# DisplayCard.net
KiCad netlist of a schematic drawn in EAGLE
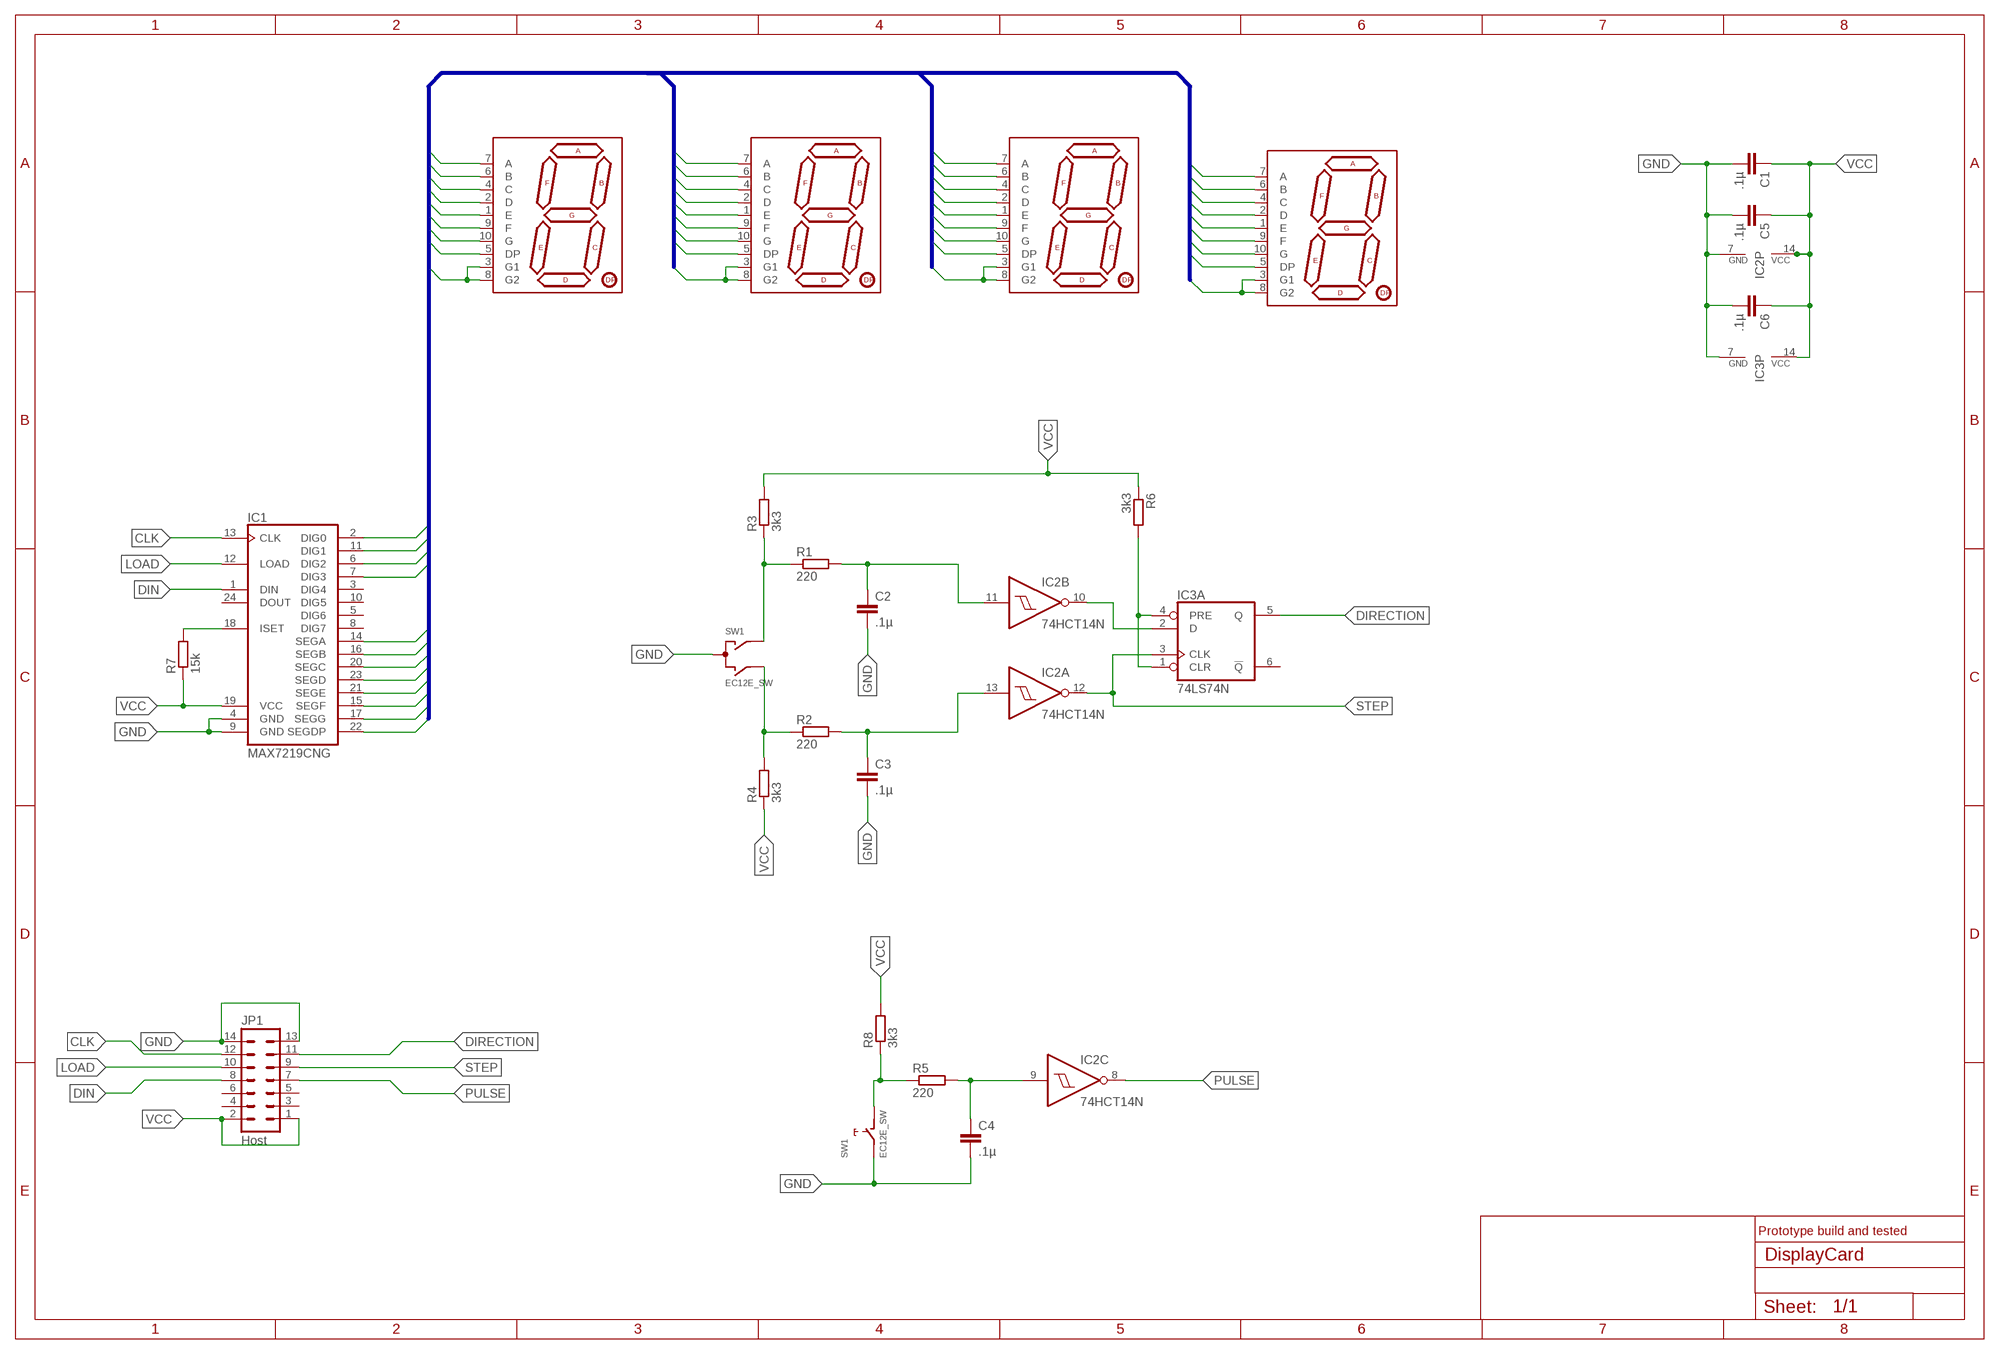
[diagram p0: schematic, sheet 1]

(export (version "E")
  (design (tool "Eeschema 10.0.6"))
  (components
    (comp (ref "C1")
      (value ".1µ")
      (footprint "eagle-import:C025-024X044")
      (libsource (lib "eagle-import") (part "resistor_C-EU025-024X044"))
    )
    (comp (ref "C2")
      (value ".1µ")
      (footprint "eagle-import:C025-024X044")
      (libsource (lib "eagle-import") (part "C-EU025-024X044"))
    )
    (comp (ref "C3")
      (value ".1µ")
      (footprint "eagle-import:C025-024X044")
      (libsource (lib "eagle-import") (part "C-EU025-024X044"))
    )
    (comp (ref "C4")
      (value ".1µ")
      (footprint "eagle-import:C025-024X044")
      (libsource (lib "eagle-import") (part "C-EU025-024X044"))
    )
    (comp (ref "C5")
      (value ".1µ")
      (footprint "eagle-import:C025-024X044")
      (libsource (lib "eagle-import") (part "resistor_C-EU025-024X044"))
    )
    (comp (ref "C6")
      (value ".1µ")
      (footprint "eagle-import:C025-024X044")
      (libsource (lib "eagle-import") (part "resistor_C-EU025-024X044"))
    )
    (comp (ref "DIGI4")
      (value "7-SEGMENT-DISPLAYPTH")
      (footprint "eagle-import:7-SEGMENT-DISPLAY")
      (libsource (lib "eagle-import") (part "7-SEGMENT-DISPLAYPTH"))
    )
    (comp (ref "DIGIT1")
      (value "7-SEGMENT-DISPLAYPTH")
      (footprint "eagle-import:7-SEGMENT-DISPLAY")
      (libsource (lib "eagle-import") (part "7-SEGMENT-DISPLAYPTH"))
    )
    (comp (ref "DIGIT2")
      (value "7-SEGMENT-DISPLAYPTH")
      (footprint "eagle-import:7-SEGMENT-DISPLAY")
      (libsource (lib "eagle-import") (part "7-SEGMENT-DISPLAYPTH"))
    )
    (comp (ref "DIGIT3")
      (value "7-SEGMENT-DISPLAYPTH")
      (footprint "eagle-import:7-SEGMENT-DISPLAY")
      (libsource (lib "eagle-import") (part "7-SEGMENT-DISPLAYPTH"))
    )
    (comp (ref "IC1")
      (value "MAX7219CNG")
      (footprint "eagle-import:DIL24-3")
      (libsource (lib "eagle-import") (part "MAX7219NGC"))
    )
    (comp (ref "IC2")
      (value "74HCT14N")
      (footprint "eagle-import:DIL14")
      (libsource (lib "eagle-import") (part "7414NHCT"))
    )
    (comp (ref "IC3")
      (value "74LS74N")
      (footprint "eagle-import:DIL14")
      (libsource (lib "eagle-import") (part "7474NLS"))
    )
    (comp (ref "JP1")
      (value "Host")
      (footprint "eagle-import:ML14L")
      (libsource (lib "eagle-import") (part "ML14L"))
    )
    (comp (ref "R1")
      (value "220")
      (footprint "eagle-import:0204_7")
      (libsource (lib "eagle-import") (part "R-EU_0204/7"))
    )
    (comp (ref "R2")
      (value "220")
      (footprint "eagle-import:0204_7")
      (libsource (lib "eagle-import") (part "R-EU_0204/7"))
    )
    (comp (ref "R3")
      (value "3k3")
      (footprint "eagle-import:0204_7")
      (libsource (lib "eagle-import") (part "R-EU_0204/7"))
    )
    (comp (ref "R4")
      (value "3k3")
      (footprint "eagle-import:0204_7")
      (libsource (lib "eagle-import") (part "R-EU_0204/7"))
    )
    (comp (ref "R5")
      (value "220")
      (footprint "eagle-import:0204_7")
      (libsource (lib "eagle-import") (part "R-EU_0204/7"))
    )
    (comp (ref "R6")
      (value "3k3")
      (footprint "eagle-import:0204_7")
      (libsource (lib "eagle-import") (part "R-EU_0204/7"))
    )
    (comp (ref "R7")
      (value "15k")
      (footprint "eagle-import:0204_7")
      (libsource (lib "eagle-import") (part "R-EU_0204/7"))
    )
    (comp (ref "R8")
      (value "3k3")
      (footprint "eagle-import:0204_7")
      (libsource (lib "eagle-import") (part "R-EU_0204/7"))
    )
    (comp (ref "SW1")
      (value "EC12E_SW")
      (footprint "eagle-import:ALPS_EC12E_SW")
      (libsource (lib "eagle-import") (part "EC12E_SW"))
    )
  )
  (nets
    (net (code "1") (name "/A") (class "Default")
      (node (ref "DIGI4") (pin "7") (pinfunction "A_7") (pintype "bidirectional"))
      (node (ref "DIGIT1") (pin "7") (pinfunction "A_7") (pintype "bidirectional"))
      (node (ref "DIGIT2") (pin "7") (pinfunction "A_7") (pintype "bidirectional"))
      (node (ref "DIGIT3") (pin "7") (pinfunction "A_7") (pintype "bidirectional"))
      (node (ref "IC1") (pin "14") (pinfunction "SEGA_14") (pintype "output"))
    )
    (net (code "2") (name "/B") (class "Default")
      (node (ref "DIGI4") (pin "6") (pinfunction "B_6") (pintype "bidirectional"))
      (node (ref "DIGIT1") (pin "6") (pinfunction "B_6") (pintype "bidirectional"))
      (node (ref "DIGIT2") (pin "6") (pinfunction "B_6") (pintype "bidirectional"))
      (node (ref "DIGIT3") (pin "6") (pinfunction "B_6") (pintype "bidirectional"))
      (node (ref "IC1") (pin "16") (pinfunction "SEGB_16") (pintype "output"))
    )
    (net (code "3") (name "/C") (class "Default")
      (node (ref "DIGI4") (pin "4") (pinfunction "C_4") (pintype "bidirectional"))
      (node (ref "DIGIT1") (pin "4") (pinfunction "C_4") (pintype "bidirectional"))
      (node (ref "DIGIT2") (pin "4") (pinfunction "C_4") (pintype "bidirectional"))
      (node (ref "DIGIT3") (pin "4") (pinfunction "C_4") (pintype "bidirectional"))
      (node (ref "IC1") (pin "20") (pinfunction "SEGC_20") (pintype "output"))
    )
    (net (code "4") (name "/D") (class "Default")
      (node (ref "DIGI4") (pin "2") (pinfunction "D_2") (pintype "bidirectional"))
      (node (ref "DIGIT1") (pin "2") (pinfunction "D_2") (pintype "bidirectional"))
      (node (ref "DIGIT2") (pin "2") (pinfunction "D_2") (pintype "bidirectional"))
      (node (ref "DIGIT3") (pin "2") (pinfunction "D_2") (pintype "bidirectional"))
      (node (ref "IC1") (pin "23") (pinfunction "SEGD_23") (pintype "output"))
    )
    (net (code "5") (name "/D0") (class "Default")
      (node (ref "DIGIT1") (pin "3") (pinfunction "G1_3") (pintype "bidirectional"))
      (node (ref "DIGIT1") (pin "8") (pinfunction "G2_8") (pintype "bidirectional"))
      (node (ref "IC1") (pin "2") (pinfunction "DIG0_2") (pintype "output"))
    )
    (net (code "6") (name "/D1") (class "Default")
      (node (ref "DIGIT2") (pin "3") (pinfunction "G1_3") (pintype "bidirectional"))
      (node (ref "DIGIT2") (pin "8") (pinfunction "G2_8") (pintype "bidirectional"))
      (node (ref "IC1") (pin "11") (pinfunction "DIG1_11") (pintype "output"))
    )
    (net (code "7") (name "/D2") (class "Default")
      (node (ref "DIGIT3") (pin "3") (pinfunction "G1_3") (pintype "bidirectional"))
      (node (ref "DIGIT3") (pin "8") (pinfunction "G2_8") (pintype "bidirectional"))
      (node (ref "IC1") (pin "6") (pinfunction "DIG2_6") (pintype "output"))
    )
    (net (code "8") (name "/D3") (class "Default")
      (node (ref "DIGI4") (pin "3") (pinfunction "G1_3") (pintype "bidirectional"))
      (node (ref "DIGI4") (pin "8") (pinfunction "G2_8") (pintype "bidirectional"))
      (node (ref "IC1") (pin "7") (pinfunction "DIG3_7") (pintype "output"))
    )
    (net (code "9") (name "/DP") (class "Default")
      (node (ref "DIGI4") (pin "5") (pinfunction "DP_5") (pintype "bidirectional"))
      (node (ref "DIGIT1") (pin "5") (pinfunction "DP_5") (pintype "bidirectional"))
      (node (ref "DIGIT2") (pin "5") (pinfunction "DP_5") (pintype "bidirectional"))
      (node (ref "IC1") (pin "22") (pinfunction "SEGDP_22") (pintype "output"))
    )
    (net (code "10") (name "/E") (class "Default")
      (node (ref "DIGI4") (pin "1") (pinfunction "E_1") (pintype "bidirectional"))
      (node (ref "DIGIT1") (pin "1") (pinfunction "E_1") (pintype "bidirectional"))
      (node (ref "DIGIT2") (pin "1") (pinfunction "E_1") (pintype "bidirectional"))
      (node (ref "DIGIT3") (pin "1") (pinfunction "E_1") (pintype "bidirectional"))
      (node (ref "IC1") (pin "21") (pinfunction "SEGE_21") (pintype "output"))
    )
    (net (code "11") (name "/F") (class "Default")
      (node (ref "DIGI4") (pin "9") (pinfunction "F_9") (pintype "bidirectional"))
      (node (ref "DIGIT1") (pin "9") (pinfunction "F_9") (pintype "bidirectional"))
      (node (ref "DIGIT2") (pin "9") (pinfunction "F_9") (pintype "bidirectional"))
      (node (ref "DIGIT3") (pin "9") (pinfunction "F_9") (pintype "bidirectional"))
      (node (ref "IC1") (pin "15") (pinfunction "SEGF_15") (pintype "output"))
    )
    (net (code "12") (name "/G") (class "Default")
      (node (ref "DIGI4") (pin "10") (pinfunction "G_10") (pintype "bidirectional"))
      (node (ref "DIGIT1") (pin "10") (pinfunction "G_10") (pintype "bidirectional"))
      (node (ref "DIGIT2") (pin "10") (pinfunction "G_10") (pintype "bidirectional"))
      (node (ref "DIGIT3") (pin "10") (pinfunction "G_10") (pintype "bidirectional"))
      (node (ref "DIGIT3") (pin "5") (pinfunction "DP_5") (pintype "bidirectional"))
      (node (ref "IC1") (pin "17") (pinfunction "SEGG_17") (pintype "output"))
    )
    (net (code "13") (name "CLK") (class "Default")
      (node (ref "IC1") (pin "13") (pinfunction "CLK_13") (pintype "input"))
      (node (ref "JP1") (pin "12") (pinfunction "12_12") (pintype "passive"))
    )
    (net (code "14") (name "DIN") (class "Default")
      (node (ref "IC1") (pin "1") (pinfunction "DIN_1") (pintype "input"))
      (node (ref "JP1") (pin "8") (pinfunction "8_8") (pintype "passive"))
    )
    (net (code "15") (name "DIRECTION") (class "Default")
      (node (ref "IC3") (pin "5") (pinfunction "Q_5") (pintype "output"))
      (node (ref "JP1") (pin "11") (pinfunction "11_11") (pintype "passive"))
    )
    (net (code "16") (name "GND") (class "Default")
      (node (ref "C1") (pin "2") (pinfunction "2_2") (pintype "passive"))
      (node (ref "C2") (pin "2") (pinfunction "2_2") (pintype "passive"))
      (node (ref "C3") (pin "2") (pinfunction "2_2") (pintype "passive"))
      (node (ref "C4") (pin "2") (pinfunction "2_2") (pintype "passive"))
      (node (ref "C5") (pin "2") (pinfunction "2_2") (pintype "passive"))
      (node (ref "C6") (pin "2") (pinfunction "2_2") (pintype "passive"))
      (node (ref "IC1") (pin "4") (pinfunction "GND_4") (pintype "power_in"))
      (node (ref "IC1") (pin "9") (pinfunction "GND_9") (pintype "power_in"))
      (node (ref "IC2") (pin "7") (pinfunction "GND_7") (pintype "power_in"))
      (node (ref "IC3") (pin "7") (pinfunction "GND_7") (pintype "power_in"))
      (node (ref "JP1") (pin "13") (pinfunction "13_13") (pintype "passive"))
      (node (ref "JP1") (pin "14") (pinfunction "14_14") (pintype "passive"))
      (node (ref "SW1") (pin "C") (pinfunction "C_C") (pintype "passive"))
      (node (ref "SW1") (pin "E") (pinfunction "2_E") (pintype "passive"))
    )
    (net (code "17") (name "LOAD") (class "Default")
      (node (ref "IC1") (pin "12") (pinfunction "LOAD_12") (pintype "input"))
      (node (ref "JP1") (pin "10") (pinfunction "10_10") (pintype "passive"))
    )
    (net (code "18") (name "Net-(IC1-ISET)") (class "Default")
      (node (ref "IC1") (pin "18") (pinfunction "ISET_18") (pintype "input"))
      (node (ref "R7") (pin "2") (pinfunction "2_2") (pintype "passive"))
    )
    (net (code "19") (name "Net-(IC2A-I)") (class "Default")
      (node (ref "C3") (pin "1") (pinfunction "1_1") (pintype "passive"))
      (node (ref "IC2") (pin "13") (pinfunction "I_13") (pintype "input"))
      (node (ref "R2") (pin "2") (pinfunction "2_2") (pintype "passive"))
    )
    (net (code "20") (name "Net-(IC2B-I)") (class "Default")
      (node (ref "C2") (pin "1") (pinfunction "1_1") (pintype "passive"))
      (node (ref "IC2") (pin "11") (pinfunction "I_11") (pintype "input"))
      (node (ref "R1") (pin "2") (pinfunction "2_2") (pintype "passive"))
    )
    (net (code "21") (name "Net-(IC2B-O)") (class "Default")
      (node (ref "IC2") (pin "10") (pinfunction "O_10") (pintype "output"))
      (node (ref "IC3") (pin "2") (pinfunction "D_2") (pintype "input"))
    )
    (net (code "22") (name "Net-(IC2C-I)") (class "Default")
      (node (ref "C4") (pin "1") (pinfunction "1_1") (pintype "passive"))
      (node (ref "IC2") (pin "9") (pinfunction "I_9") (pintype "input"))
      (node (ref "R5") (pin "2") (pinfunction "2_2") (pintype "passive"))
    )
    (net (code "23") (name "Net-(IC3A-CLR)") (class "Default")
      (node (ref "IC3") (pin "1") (pinfunction "CLR_1") (pintype "input"))
      (node (ref "IC3") (pin "4") (pinfunction "PRE_4") (pintype "input"))
      (node (ref "R6") (pin "2") (pinfunction "2_2") (pintype "passive"))
    )
    (net (code "24") (name "Net-(R1-Pad1)") (class "Default")
      (node (ref "R1") (pin "1") (pinfunction "1_1") (pintype "passive"))
      (node (ref "R3") (pin "1") (pinfunction "1_1") (pintype "passive"))
      (node (ref "SW1") (pin "A") (pinfunction "A_A") (pintype "passive"))
    )
    (net (code "25") (name "Net-(R2-Pad1)") (class "Default")
      (node (ref "R2") (pin "1") (pinfunction "1_1") (pintype "passive"))
      (node (ref "R4") (pin "2") (pinfunction "2_2") (pintype "passive"))
      (node (ref "SW1") (pin "B") (pinfunction "B_B") (pintype "passive"))
    )
    (net (code "26") (name "Net-(SW1B-1)") (class "Default")
      (node (ref "R5") (pin "1") (pinfunction "1_1") (pintype "passive"))
      (node (ref "R8") (pin "1") (pinfunction "1_1") (pintype "passive"))
      (node (ref "SW1") (pin "D") (pinfunction "1_D") (pintype "passive"))
    )
    (net (code "27") (name "PULSE") (class "Default")
      (node (ref "IC2") (pin "8") (pinfunction "O_8") (pintype "output"))
      (node (ref "JP1") (pin "7") (pinfunction "7_7") (pintype "passive"))
    )
    (net (code "28") (name "STEP") (class "Default")
      (node (ref "IC2") (pin "12") (pinfunction "O_12") (pintype "output"))
      (node (ref "IC3") (pin "3") (pinfunction "CLK_3") (pintype "input"))
      (node (ref "JP1") (pin "9") (pinfunction "9_9") (pintype "passive"))
    )
    (net (code "29") (name "VCC") (class "Default")
      (node (ref "C1") (pin "1") (pinfunction "1_1") (pintype "passive"))
      (node (ref "C5") (pin "1") (pinfunction "1_1") (pintype "passive"))
      (node (ref "C6") (pin "1") (pinfunction "1_1") (pintype "passive"))
      (node (ref "IC1") (pin "19") (pinfunction "VCC_19") (pintype "power_in"))
      (node (ref "IC2") (pin "14") (pinfunction "VCC_14") (pintype "power_in"))
      (node (ref "IC3") (pin "14") (pinfunction "VCC_14") (pintype "power_in"))
      (node (ref "JP1") (pin "1") (pinfunction "1_1") (pintype "passive"))
      (node (ref "JP1") (pin "2") (pinfunction "2_2") (pintype "passive"))
      (node (ref "R3") (pin "2") (pinfunction "2_2") (pintype "passive"))
      (node (ref "R4") (pin "1") (pinfunction "1_1") (pintype "passive"))
      (node (ref "R6") (pin "1") (pinfunction "1_1") (pintype "passive"))
      (node (ref "R7") (pin "1") (pinfunction "1_1") (pintype "passive"))
      (node (ref "R8") (pin "2") (pinfunction "2_2") (pintype "passive"))
    )
    (net (code "30") (name "unconnected-(IC1-DIG4-Pad3)") (class "Default")
      (node (ref "IC1") (pin "3") (pinfunction "DIG4_3") (pintype "output"))
    )
    (net (code "31") (name "unconnected-(IC1-DIG5-Pad10)") (class "Default")
      (node (ref "IC1") (pin "10") (pinfunction "DIG5_10") (pintype "output"))
    )
    (net (code "32") (name "unconnected-(IC1-DIG6-Pad5)") (class "Default")
      (node (ref "IC1") (pin "5") (pinfunction "DIG6_5") (pintype "output"))
    )
    (net (code "33") (name "unconnected-(IC1-DIG7-Pad8)") (class "Default")
      (node (ref "IC1") (pin "8") (pinfunction "DIG7_8") (pintype "output"))
    )
    (net (code "34") (name "unconnected-(IC1-DOUT-Pad24)") (class "Default")
      (node (ref "IC1") (pin "24") (pinfunction "DOUT_24") (pintype "output"))
    )
    (net (code "35") (name "unconnected-(IC3A-~{Q}-Pad6)") (class "Default")
      (node (ref "IC3") (pin "6") (pinfunction "~{Q}_6") (pintype "output"))
    )
    (net (code "36") (name "unconnected-(JP1-Pad3)") (class "Default")
      (node (ref "JP1") (pin "3") (pinfunction "3_3") (pintype "passive"))
    )
    (net (code "37") (name "unconnected-(JP1-Pad4)") (class "Default")
      (node (ref "JP1") (pin "4") (pinfunction "4_4") (pintype "passive"))
    )
    (net (code "38") (name "unconnected-(JP1-Pad5)") (class "Default")
      (node (ref "JP1") (pin "5") (pinfunction "5_5") (pintype "passive"))
    )
    (net (code "39") (name "unconnected-(JP1-Pad6)") (class "Default")
      (node (ref "JP1") (pin "6") (pinfunction "6_6") (pintype "passive"))
    )
  )
)
